# IR.net
KiCad netlist of a schematic drawn in Altium Designer
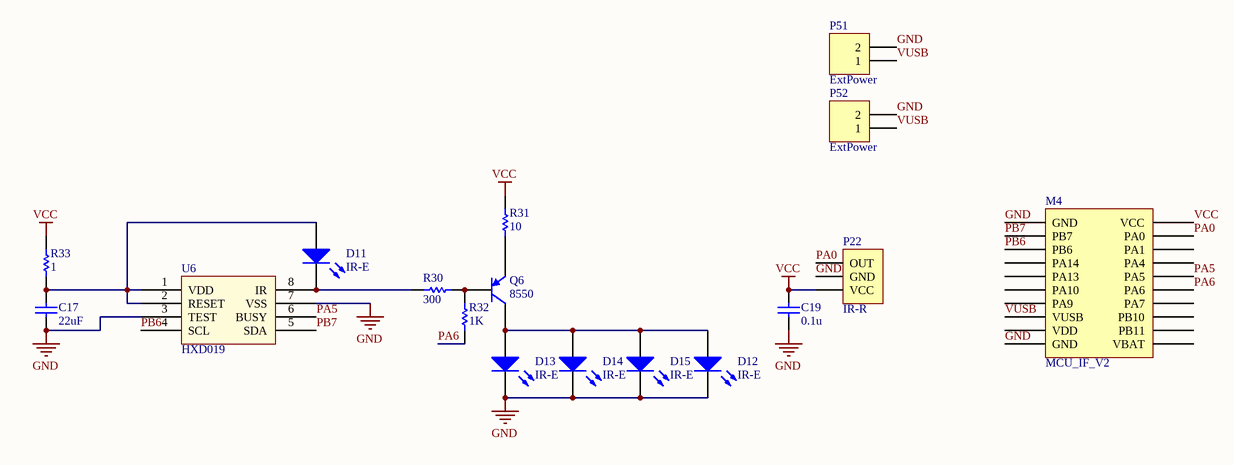
[diagram p0: IR.SchDoc]

(export (version "E")
  (design (tool "Eeschema 10.0.6"))
  (components
    (comp (ref "C17")
      (value "22uF")
      (footprint "C-2012[0805]")
      (description "Capacitor (Semiconductor SIM Model)")
      (fields (field (name "Comment") "Cap Semi") (field (name "PUBLISHER") "Altium Limited"))
      (libsource (lib "Miscellaneous Devices") (part "Cap Semi"))
    )
    (comp (ref "C19")
      (value "0.1u")
      (footprint "C-1608[0603]")
      (description "Capacitor (Semiconductor SIM Model)")
      (fields (field (name "Comment") "Cap Semi") (field (name "PUBLISHER") "Altium Limited"))
      (libsource (lib "Miscellaneous Devices") (part "Cap Semi"))
    )
    (comp (ref "D11")
      (value "IR-E")
      (footprint "PIN2")
      (description "Typical INFRARED GaAs LED")
      (fields (field (name "PUBLISHER") "Altium Limited"))
      (libsource (lib "Miscellaneous Devices") (part "LED0"))
    )
    (comp (ref "D12")
      (value "IR-E")
      (footprint "PIN2")
      (description "Typical INFRARED GaAs LED")
      (fields (field (name "PUBLISHER") "Altium Limited"))
      (libsource (lib "Miscellaneous Devices") (part "LED0"))
    )
    (comp (ref "D13")
      (value "IR-E")
      (footprint "PIN2")
      (description "Typical INFRARED GaAs LED")
      (fields (field (name "PUBLISHER") "Altium Limited"))
      (libsource (lib "Miscellaneous Devices") (part "LED0"))
    )
    (comp (ref "D14")
      (value "IR-E")
      (footprint "PIN2")
      (description "Typical INFRARED GaAs LED")
      (fields (field (name "PUBLISHER") "Altium Limited"))
      (libsource (lib "Miscellaneous Devices") (part "LED0"))
    )
    (comp (ref "D15")
      (value "IR-E")
      (footprint "PIN2")
      (description "Typical INFRARED GaAs LED")
      (fields (field (name "PUBLISHER") "Altium Limited"))
      (libsource (lib "Miscellaneous Devices") (part "LED0"))
    )
    (comp (ref "M4")
      (value "MCU_IF_V2")
      (footprint "MCU_IF_V2")
      (libsource (lib "MCU_IF") (part "MCU_IF_V1"))
    )
    (comp (ref "P22")
      (value "IR-R")
      (footprint "HDR1X3")
      (description "Header, 3-Pin")
      (fields (field (name "PUBLISHER") "Altium Limited"))
      (libsource (lib "sensor_ifce") (part "IR"))
    )
    (comp (ref "P51")
      (value "ExtPower")
      (footprint "HDR1X2H")
      (description "Header, 2-Pin, Right Angle")
      (fields (field (name "PUBLISHER") "Altium Limited"))
      (libsource (lib "Miscellaneous Connectors") (part "Header 2H"))
    )
    (comp (ref "P52")
      (value "ExtPower")
      (footprint "HDR1X2H")
      (description "Header, 2-Pin, Right Angle")
      (fields (field (name "PUBLISHER") "Altium Limited"))
      (libsource (lib "Miscellaneous Connectors") (part "Header 2H"))
    )
    (comp (ref "Q6")
      (value "8550")
      (footprint "SOT-23B")
      (description "PNP Bipolar Transistor")
      (fields (field (name "PUBLISHER") "Altium Limited"))
      (libsource (lib "Miscellaneous Devices") (part "PNP"))
    )
    (comp (ref "R30")
      (value "300")
      (footprint "R-1608[0603]")
      (description "Semiconductor Resistor")
      (fields (field (name "Comment") "Res Semi") (field (name "PUBLISHER") "Altium Limited"))
      (libsource (lib "Miscellaneous Devices") (part "Res Semi"))
    )
    (comp (ref "R31")
      (value "10")
      (footprint "R-2012[0805]")
      (description "Semiconductor Resistor")
      (fields (field (name "Comment") "Res Semi") (field (name "PUBLISHER") "Altium Limited"))
      (libsource (lib "Miscellaneous Devices") (part "Res Semi"))
    )
    (comp (ref "R32")
      (value "1K")
      (footprint "R-1608[0603]")
      (description "Semiconductor Resistor")
      (fields (field (name "Comment") "Res Semi") (field (name "PUBLISHER") "Altium Limited"))
      (libsource (lib "Miscellaneous Devices") (part "Res Semi"))
    )
    (comp (ref "R33")
      (value "1")
      (footprint "R-2012[0805]")
      (description "Semiconductor Resistor")
      (fields (field (name "Comment") "Res Semi") (field (name "PUBLISHER") "Altium Limited"))
      (libsource (lib "Miscellaneous Devices") (part "Res Semi"))
    )
    (comp (ref "U6") (value "HXD019") (footprint "SOP8") (libsource (lib "HXD019") (part "HXD019")))
  )
  (nets
    (net (code "1") (name "/PA0") (class "Default")
      (node (ref "M4") (pin "19") (pinfunction "PA0_19") (pintype "passive"))
      (node (ref "P22") (pin "1") (pinfunction "OUT_1") (pintype "passive"))
    )
    (net (code "2") (name "/PA5") (class "Default")
      (node (ref "M4") (pin "16") (pinfunction "PA5_16") (pintype "passive"))
      (node (ref "U6") (pin "6") (pinfunction "BUSY_6") (pintype "passive"))
    )
    (net (code "3") (name "/PA6") (class "Default")
      (node (ref "M4") (pin "15") (pinfunction "PA6_15") (pintype "passive"))
      (node (ref "R32") (pin "1") (pinfunction "1_1") (pintype "passive"))
    )
    (net (code "4") (name "/PB6") (class "Default")
      (node (ref "M4") (pin "3") (pinfunction "PB6_3") (pintype "passive"))
      (node (ref "U6") (pin "4") (pinfunction "SCL_4") (pintype "passive"))
    )
    (net (code "5") (name "/PB7") (class "Default")
      (node (ref "M4") (pin "2") (pinfunction "PB7_2") (pintype "passive"))
      (node (ref "U6") (pin "5") (pinfunction "SDA_5") (pintype "passive"))
    )
    (net (code "6") (name "/VUSB") (class "Default")
      (node (ref "M4") (pin "8") (pinfunction "VUSB_8") (pintype "passive"))
      (node (ref "P51") (pin "1") (pinfunction "1_1") (pintype "passive"))
      (node (ref "P52") (pin "1") (pinfunction "1_1") (pintype "passive"))
    )
    (net (code "7") (name "GND") (class "Default")
      (node (ref "C17") (pin "2") (pinfunction "2_2") (pintype "passive"))
      (node (ref "C19") (pin "1") (pinfunction "1_1") (pintype "passive"))
      (node (ref "D12") (pin "2") (pinfunction "K_2") (pintype "passive"))
      (node (ref "D13") (pin "2") (pinfunction "K_2") (pintype "passive"))
      (node (ref "D14") (pin "2") (pinfunction "K_2") (pintype "passive"))
      (node (ref "D15") (pin "2") (pinfunction "K_2") (pintype "passive"))
      (node (ref "M4") (pin "1") (pinfunction "GND_1") (pintype "passive"))
      (node (ref "M4") (pin "10") (pinfunction "GND_10") (pintype "passive"))
      (node (ref "P22") (pin "2") (pinfunction "GND_2") (pintype "passive"))
      (node (ref "P51") (pin "2") (pinfunction "2_2") (pintype "passive"))
      (node (ref "P52") (pin "2") (pinfunction "2_2") (pintype "passive"))
      (node (ref "U6") (pin "3") (pinfunction "TEST_3") (pintype "passive"))
      (node (ref "U6") (pin "7") (pinfunction "VSS_7") (pintype "passive"))
    )
    (net (code "8") (name "Net-(D11-A)") (class "Default")
      (node (ref "C17") (pin "1") (pinfunction "1_1") (pintype "passive"))
      (node (ref "D11") (pin "1") (pinfunction "A_1") (pintype "passive"))
      (node (ref "R33") (pin "2") (pinfunction "2_2") (pintype "passive"))
      (node (ref "U6") (pin "1") (pinfunction "VDD_1") (pintype "passive"))
      (node (ref "U6") (pin "2") (pinfunction "RESET_2") (pintype "passive"))
    )
    (net (code "9") (name "Net-(D11-K)") (class "Default")
      (node (ref "D11") (pin "2") (pinfunction "K_2") (pintype "passive"))
      (node (ref "R30") (pin "1") (pinfunction "1_1") (pintype "passive"))
      (node (ref "U6") (pin "8") (pinfunction "IR_8") (pintype "passive"))
    )
    (net (code "10") (name "Net-(D12-A)") (class "Default")
      (node (ref "D12") (pin "1") (pinfunction "A_1") (pintype "passive"))
      (node (ref "D13") (pin "1") (pinfunction "A_1") (pintype "passive"))
      (node (ref "D14") (pin "1") (pinfunction "A_1") (pintype "passive"))
      (node (ref "D15") (pin "1") (pinfunction "A_1") (pintype "passive"))
      (node (ref "Q6") (pin "1") (pinfunction "C_1") (pintype "passive"))
    )
    (net (code "11") (name "Net-(Q6-B)") (class "Default")
      (node (ref "Q6") (pin "2") (pinfunction "B_2") (pintype "passive"))
      (node (ref "R30") (pin "2") (pinfunction "2_2") (pintype "passive"))
      (node (ref "R32") (pin "2") (pinfunction "2_2") (pintype "passive"))
    )
    (net (code "12") (name "Net-(Q6-E)") (class "Default")
      (node (ref "Q6") (pin "3") (pinfunction "E_3") (pintype "passive"))
      (node (ref "R31") (pin "2") (pinfunction "2_2") (pintype "passive"))
    )
    (net (code "13") (name "VCC") (class "Default")
      (node (ref "C19") (pin "2") (pinfunction "2_2") (pintype "passive"))
      (node (ref "M4") (pin "20") (pinfunction "VCC_20") (pintype "passive"))
      (node (ref "P22") (pin "3") (pinfunction "VCC_3") (pintype "passive"))
      (node (ref "R31") (pin "1") (pinfunction "1_1") (pintype "passive"))
      (node (ref "R33") (pin "1") (pinfunction "1_1") (pintype "passive"))
    )
    (net (code "14") (name "unconnected-(M4-PA1-Pad18)") (class "Default")
      (node (ref "M4") (pin "18") (pinfunction "PA1_18") (pintype "passive"))
    )
    (net (code "15") (name "unconnected-(M4-PA4-Pad17)") (class "Default")
      (node (ref "M4") (pin "17") (pinfunction "PA4_17") (pintype "passive"))
    )
    (net (code "16") (name "unconnected-(M4-PA7-Pad14)") (class "Default")
      (node (ref "M4") (pin "14") (pinfunction "PA7_14") (pintype "passive"))
    )
    (net (code "17") (name "unconnected-(M4-PA9-Pad7)") (class "Default")
      (node (ref "M4") (pin "7") (pinfunction "PA9_7") (pintype "passive"))
    )
    (net (code "18") (name "unconnected-(M4-PA10-Pad6)") (class "Default")
      (node (ref "M4") (pin "6") (pinfunction "PA10_6") (pintype "passive"))
    )
    (net (code "19") (name "unconnected-(M4-PA13-Pad5)") (class "Default")
      (node (ref "M4") (pin "5") (pinfunction "PA13_5") (pintype "passive"))
    )
    (net (code "20") (name "unconnected-(M4-PA14-Pad4)") (class "Default")
      (node (ref "M4") (pin "4") (pinfunction "PA14_4") (pintype "passive"))
    )
    (net (code "21") (name "unconnected-(M4-PB10-Pad13)") (class "Default")
      (node (ref "M4") (pin "13") (pinfunction "PB10_13") (pintype "passive"))
    )
    (net (code "22") (name "unconnected-(M4-PB11-Pad12)") (class "Default")
      (node (ref "M4") (pin "12") (pinfunction "PB11_12") (pintype "passive"))
    )
    (net (code "23") (name "unconnected-(M4-VBAT-Pad11)") (class "Default")
      (node (ref "M4") (pin "11") (pinfunction "VBAT_11") (pintype "passive"))
    )
    (net (code "24") (name "unconnected-(M4-VDD-Pad9)") (class "Default")
      (node (ref "M4") (pin "9") (pinfunction "VDD_9") (pintype "passive"))
    )
  )
)
